# -24V-8_V0_2.net
KiCad netlist of a schematic drawn in Altium Designer
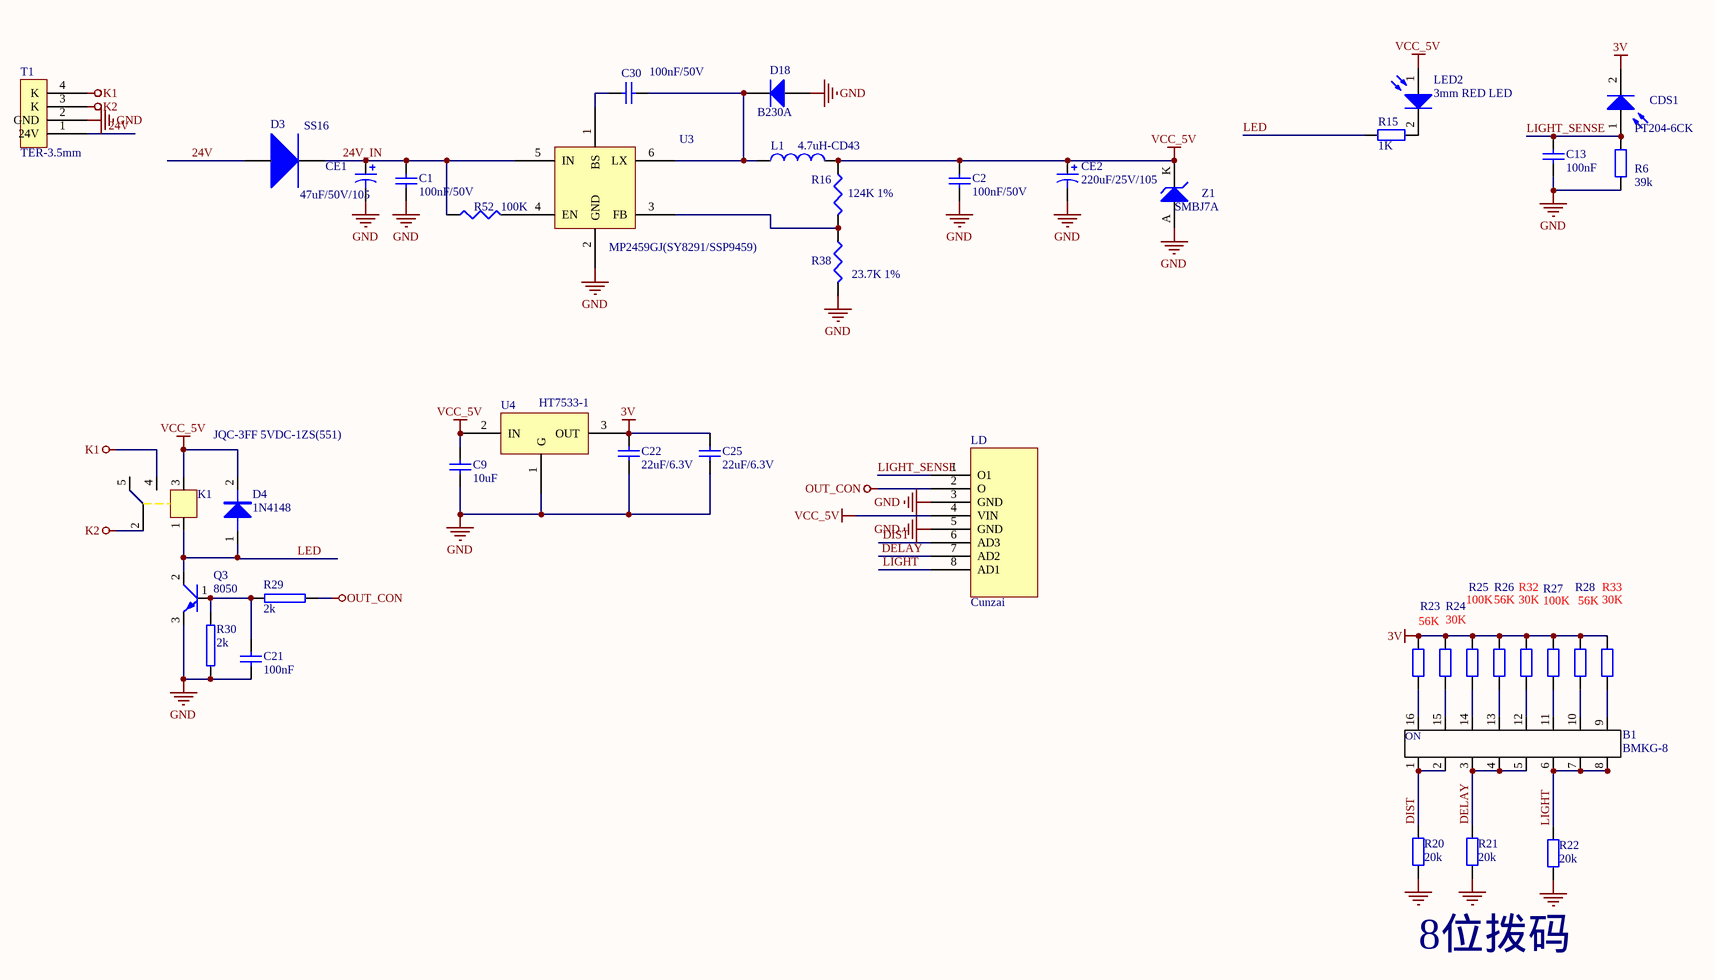
[diagram p0: 存在感应灯控模块-24V-8位拨码V0.2.schdoc]

(export (version "E")
  (design (tool "Eeschema 10.0.6"))
  (components
    (comp (ref "B1") (value "BMKG-8") (footprint "BMKG-8") (libsource (lib "灯控模组V2.0") (part "BMKG-8")))
    (comp (ref "C1")
      (value "100nF/50V")
      (footprint "0603")
      (description "Capacitor (Semiconductor SIM Model)")
      (fields (field (name "PUBLISHER") "Altium Limited"))
      (libsource (lib "Miscellaneous Devices") (part "Cap Semi"))
    )
    (comp (ref "C2")
      (value "100nF/50V")
      (footprint "0603")
      (description "Capacitor (Semiconductor SIM Model)")
      (fields (field (name "PUBLISHER") "Altium Limited"))
      (libsource (lib "Miscellaneous Devices") (part "Cap Semi"))
    )
    (comp (ref "C9")
      (value "10uF")
      (footprint "C0603")
      (description "Capacitor")
      (fields (field (name "PUBLISHER") "Altium Limited"))
      (libsource (lib "Miscellaneous Devices") (part "Cap"))
    )
    (comp (ref "C13")
      (value "100nF")
      (footprint "C0603")
      (description "Capacitor")
      (fields (field (name "PUBLISHER") "Altium Limited"))
      (libsource (lib "Miscellaneous Devices") (part "Cap"))
    )
    (comp (ref "C21")
      (value "100nF")
      (footprint "C0603")
      (description "Capacitor")
      (fields (field (name "PUBLISHER") "Altium Limited"))
      (libsource (lib "Miscellaneous Devices") (part "Cap"))
    )
    (comp (ref "C22")
      (value "22uF/6.3V")
      (footprint "C0603")
      (description "Capacitor")
      (fields (field (name "PUBLISHER") "Altium Limited"))
      (libsource (lib "Miscellaneous Devices") (part "Cap"))
    )
    (comp (ref "C25")
      (value "22uF/6.3V")
      (footprint "C0603")
      (description "Capacitor")
      (fields (field (name "PUBLISHER") "Altium Limited"))
      (libsource (lib "Miscellaneous Devices") (part "Cap"))
    )
    (comp (ref "C30")
      (value "100nF/50V")
      (footprint "0603")
      (description "Capacitor (Semiconductor SIM Model)")
      (fields (field (name "PUBLISHER") "Altium Limited"))
      (libsource (lib "Miscellaneous Devices") (part "Cap Semi"))
    )
    (comp (ref "CDS1")
      (value "PT204-6CK")
      (footprint "LED-3MM")
      (description "Photosensitive Diode")
      (fields (field (name "PUBLISHER") "Altium Limited"))
      (libsource (lib "Miscellaneous Devices") (part "Photo Sen"))
    )
    (comp (ref "CE1")
      (value "47uF/50V/105")
      (footprint "DIPC6X12")
      (description "Polarized Capacitor (Radial)")
      (fields (field (name "PUBLISHER") "Altium Limited"))
      (libsource (lib "Miscellaneous Devices") (part "Cap Pol1"))
    )
    (comp (ref "CE2")
      (value "220uF/25V/105")
      (footprint "DIPC6X12")
      (description "Polarized Capacitor (Radial)")
      (fields (field (name "PUBLISHER") "Altium Limited"))
      (libsource (lib "Miscellaneous Devices") (part "Cap Pol1"))
    )
    (comp (ref "D3") (value "SS16") (footprint "SMA") (libsource (lib "微波红外双鉴电路") (part "SS14")))
    (comp (ref "D4")
      (value "1N4148")
      (footprint "SOD123")
      (description "Diode")
      (libsource (lib "*") (part "DIODE"))
    )
    (comp (ref "D18")
      (value "B230A")
      (footprint "SMA")
      (description "1 Amp General Purpose Rectifier")
      (fields (field (name "PUBLISHER") "Altium Limited"))
      (libsource (lib "Miscellaneous Devices") (part "Diode 1N4007"))
    )
    (comp (ref "K1") (value "JQC-3FF 5VDC-1ZS(551)") (footprint "JQC-3FF") (libsource (lib "*") (part "JDQ")))
    (comp (ref "L1")
      (value "4.7uH-CD43")
      (footprint "CDRH3D16")
      (description "Inductor")
      (fields (field (name "PUBLISHER") "Altium Limited"))
      (libsource (lib "Miscellaneous Devices") (part "Inductor"))
    )
    (comp (ref "LD")
      (value "Cunzai")
      (footprint "LDCUNZAI")
      (libsource (lib "存在感应灯控模块-24V-8位拨码") (part "Cunzai"))
    )
    (comp (ref "LED2")
      (value "3mm RED LED")
      (footprint "LED-3MM")
      (description "Photosensitive Diode")
      (fields (field (name "PUBLISHER") "Altium Limited"))
      (libsource (lib "Miscellaneous Devices") (part "Photo Sen"))
    )
    (comp (ref "Q3") (value "8050") (footprint "SOT23") (libsource (lib "*") (part "8050")))
    (comp (ref "R6")
      (value "39k")
      (footprint "R0603")
      (description "Resistor")
      (fields (field (name "Comment") "Res2") (field (name "PUBLISHER") "Altium Limited"))
      (libsource (lib "Miscellaneous Devices") (part "Res2"))
    )
    (comp (ref "R15")
      (value "1K")
      (footprint "R0603")
      (description "Resistor")
      (fields (field (name "Comment") "Res2") (field (name "PUBLISHER") "Altium Limited"))
      (libsource (lib "") (part "Res2_1"))
    )
    (comp (ref "R16")
      (value "124K 1%")
      (footprint "0603")
      (description "Resistor")
      (fields (field (name "PUBLISHER") "Altium Limited"))
      (libsource (lib "Miscellaneous Devices") (part "Res3"))
    )
    (comp (ref "R20")
      (value "20k")
      (footprint "R0603")
      (description "Resistor")
      (fields (field (name "PUBLISHER") "Altium Limited"))
      (libsource (lib "*") (part "Res2"))
    )
    (comp (ref "R21")
      (value "20k")
      (footprint "R0603")
      (description "Resistor")
      (fields (field (name "PUBLISHER") "Altium Limited"))
      (libsource (lib "*") (part "Res2"))
    )
    (comp (ref "R22")
      (value "20k")
      (footprint "R0603")
      (description "Resistor")
      (fields (field (name "PUBLISHER") "Altium Limited"))
      (libsource (lib "*") (part "Res2"))
    )
    (comp (ref "R23")
      (value "56K")
      (footprint "R0603")
      (description "Resistor")
      (fields (field (name "PUBLISHER") "Altium Limited"))
      (libsource (lib "*") (part "Res2"))
    )
    (comp (ref "R24")
      (value "30K")
      (footprint "R0603")
      (description "Resistor")
      (fields (field (name "PUBLISHER") "Altium Limited"))
      (libsource (lib "*") (part "Res2"))
    )
    (comp (ref "R25")
      (value "100K")
      (footprint "R0603")
      (description "Resistor")
      (fields (field (name "PUBLISHER") "Altium Limited"))
      (libsource (lib "*") (part "Res2"))
    )
    (comp (ref "R26")
      (value "56K")
      (footprint "R0603")
      (description "Resistor")
      (fields (field (name "PUBLISHER") "Altium Limited"))
      (libsource (lib "*") (part "Res2"))
    )
    (comp (ref "R27")
      (value "100K")
      (footprint "R0603")
      (description "Resistor")
      (fields (field (name "PUBLISHER") "Altium Limited"))
      (libsource (lib "*") (part "Res2"))
    )
    (comp (ref "R28")
      (value "56K")
      (footprint "R0603")
      (description "Resistor")
      (fields (field (name "PUBLISHER") "Altium Limited"))
      (libsource (lib "*") (part "Res2"))
    )
    (comp (ref "R29") (value "2k") (footprint "SR0603") (libsource (lib "*") (part "RES")))
    (comp (ref "R30") (value "2k") (footprint "SR0603") (libsource (lib "*") (part "RES")))
    (comp (ref "R32")
      (value "30K")
      (footprint "R0603")
      (description "Resistor")
      (fields (field (name "PUBLISHER") "Altium Limited"))
      (libsource (lib "*") (part "Res2"))
    )
    (comp (ref "R33")
      (value "30K")
      (footprint "R0603")
      (description "Resistor")
      (fields (field (name "PUBLISHER") "Altium Limited"))
      (libsource (lib "*") (part "Res2"))
    )
    (comp (ref "R38")
      (value "23.7K 1%")
      (footprint "0603")
      (description "Resistor")
      (fields (field (name "PUBLISHER") "Altium Limited"))
      (libsource (lib "Miscellaneous Devices") (part "Res3"))
    )
    (comp (ref "R52")
      (value "100K")
      (footprint "0603")
      (description "Resistor")
      (fields (field (name "PUBLISHER") "Altium Limited"))
      (libsource (lib "Miscellaneous Devices") (part "Res3"))
    )
    (comp (ref "T1")
      (value "TER-3.5mm")
      (footprint "4-KKK")
      (libsource (lib "灯控模块-V3.3-(101&102&100-2)-24V-8位拨码") (part "TER-3.5mm"))
    )
    (comp (ref "U3")
      (value "MP2459GJ(SY8291/SSP9459)")
      (footprint "SOT23-6")
      (libsource (lib "SPECIAL-L-V6.6") (part "SY8120B"))
    )
    (comp (ref "U4") (value "HT7533-1") (footprint "SOT-89") (libsource (lib "MYLIB") (part "12S33")))
    (comp (ref "Z1")
      (value "SMBJ7A")
      (footprint "SMB")
      (description "Zener Diode")
      (fields (field (name "PUBLISHER") "Altium Limited"))
      (libsource (lib "Miscellaneous Devices") (part "D Zener"))
    )
  )
  (nets
    (net (code "1") (name "/24V") (class "Default")
      (node (ref "D3") (pin "1") (pinfunction "B_1") (pintype "passive"))
      (node (ref "T1") (pin "1") (pinfunction "24V_1") (pintype "passive"))
    )
    (net (code "2") (name "/24V_IN") (class "Default")
      (node (ref "C1") (pin "2") (pinfunction "2_2") (pintype "passive"))
      (node (ref "CE1") (pin "1") (pinfunction "1_1") (pintype "passive"))
      (node (ref "D3") (pin "2") (pinfunction "C_2") (pintype "passive"))
      (node (ref "R52") (pin "1") (pinfunction "1_1") (pintype "passive"))
      (node (ref "U3") (pin "5") (pinfunction "IN_5") (pintype "passive"))
    )
    (net (code "3") (name "/DELAY") (class "Default")
      (node (ref "B1") (pin "3") (pintype "passive"))
      (node (ref "B1") (pin "4") (pintype "passive"))
      (node (ref "B1") (pin "5") (pintype "passive"))
      (node (ref "LD") (pin "7") (pinfunction "AD2_7") (pintype "passive"))
      (node (ref "R21") (pin "2") (pinfunction "2_2") (pintype "passive"))
    )
    (net (code "4") (name "/DIST") (class "Default")
      (node (ref "B1") (pin "1") (pintype "passive"))
      (node (ref "B1") (pin "2") (pintype "passive"))
      (node (ref "LD") (pin "6") (pinfunction "AD3_6") (pintype "passive"))
      (node (ref "R20") (pin "2") (pinfunction "2_2") (pintype "passive"))
    )
    (net (code "5") (name "/LED") (class "Default")
      (node (ref "D4") (pin "1") (pintype "passive"))
      (node (ref "K1") (pin "1") (pintype "passive"))
      (node (ref "Q3") (pin "2") (pinfunction "E_2") (pintype "passive"))
      (node (ref "R15") (pin "2") (pinfunction "2_2") (pintype "passive"))
    )
    (net (code "6") (name "/LIGHT") (class "Default")
      (node (ref "B1") (pin "6") (pintype "passive"))
      (node (ref "B1") (pin "7") (pintype "passive"))
      (node (ref "B1") (pin "8") (pintype "passive"))
      (node (ref "LD") (pin "8") (pinfunction "AD1_8") (pintype "passive"))
      (node (ref "R22") (pin "2") (pinfunction "2_2") (pintype "passive"))
    )
    (net (code "7") (name "/LIGHT_SENSE") (class "Default")
      (node (ref "C13") (pin "2") (pinfunction "2_2") (pintype "passive"))
      (node (ref "CDS1") (pin "1") (pinfunction "A_1") (pintype "passive"))
      (node (ref "LD") (pin "1") (pinfunction "O1_1") (pintype "passive"))
      (node (ref "R6") (pin "2") (pinfunction "2_2") (pintype "passive"))
    )
    (net (code "8") (name "3V") (class "Default")
      (node (ref "C22") (pin "1") (pinfunction "1_1") (pintype "passive"))
      (node (ref "C25") (pin "1") (pinfunction "1_1") (pintype "passive"))
      (node (ref "CDS1") (pin "2") (pinfunction "K_2") (pintype "passive"))
      (node (ref "R23") (pin "2") (pinfunction "2_2") (pintype "passive"))
      (node (ref "R24") (pin "2") (pinfunction "2_2") (pintype "passive"))
      (node (ref "R25") (pin "2") (pinfunction "2_2") (pintype "passive"))
      (node (ref "R26") (pin "2") (pinfunction "2_2") (pintype "passive"))
      (node (ref "R27") (pin "2") (pinfunction "2_2") (pintype "passive"))
      (node (ref "R28") (pin "2") (pinfunction "2_2") (pintype "passive"))
      (node (ref "R32") (pin "2") (pinfunction "2_2") (pintype "passive"))
      (node (ref "R33") (pin "2") (pinfunction "2_2") (pintype "passive"))
      (node (ref "U4") (pin "3") (pinfunction "OUT_3") (pintype "passive"))
    )
    (net (code "9") (name "GND") (class "Default")
      (node (ref "C1") (pin "1") (pinfunction "1_1") (pintype "passive"))
      (node (ref "C13") (pin "1") (pinfunction "1_1") (pintype "passive"))
      (node (ref "C2") (pin "1") (pinfunction "1_1") (pintype "passive"))
      (node (ref "C21") (pin "2") (pinfunction "2_2") (pintype "passive"))
      (node (ref "C22") (pin "2") (pinfunction "2_2") (pintype "passive"))
      (node (ref "C25") (pin "2") (pinfunction "2_2") (pintype "passive"))
      (node (ref "C9") (pin "2") (pinfunction "2_2") (pintype "passive"))
      (node (ref "CE1") (pin "2") (pinfunction "2_2") (pintype "passive"))
      (node (ref "CE2") (pin "2") (pinfunction "2_2") (pintype "passive"))
      (node (ref "D18") (pin "1") (pinfunction "A_1") (pintype "passive"))
      (node (ref "LD") (pin "3") (pinfunction "GND_3") (pintype "passive"))
      (node (ref "LD") (pin "5") (pinfunction "GND_5") (pintype "passive"))
      (node (ref "Q3") (pin "3") (pinfunction "C_3") (pintype "passive"))
      (node (ref "R20") (pin "1") (pinfunction "1_1") (pintype "passive"))
      (node (ref "R21") (pin "1") (pinfunction "1_1") (pintype "passive"))
      (node (ref "R22") (pin "1") (pinfunction "1_1") (pintype "passive"))
      (node (ref "R30") (pin "1") (pinfunction "1_1") (pintype "passive"))
      (node (ref "R38") (pin "2") (pinfunction "2_2") (pintype "passive"))
      (node (ref "R6") (pin "1") (pinfunction "1_1") (pintype "passive"))
      (node (ref "T1") (pin "2") (pinfunction "GND_2") (pintype "passive"))
      (node (ref "U3") (pin "2") (pinfunction "GND_2") (pintype "passive"))
      (node (ref "U4") (pin "1") (pinfunction "G_1") (pintype "passive"))
      (node (ref "Z1") (pin "A") (pinfunction "A_A") (pintype "passive"))
    )
    (net (code "10") (name "K1") (class "Default")
      (node (ref "K1") (pin "4") (pintype "passive"))
      (node (ref "T1") (pin "4") (pinfunction "K_4") (pintype "passive"))
    )
    (net (code "11") (name "K2") (class "Default")
      (node (ref "K1") (pin "2") (pintype "passive"))
      (node (ref "T1") (pin "3") (pinfunction "K_3") (pintype "passive"))
    )
    (net (code "12") (name "Net-(B1-Pad9)") (class "Default")
      (node (ref "B1") (pin "9") (pintype "passive"))
      (node (ref "R33") (pin "1") (pinfunction "1_1") (pintype "passive"))
    )
    (net (code "13") (name "Net-(B1-Pad10)") (class "Default")
      (node (ref "B1") (pin "10") (pintype "passive"))
      (node (ref "R28") (pin "1") (pinfunction "1_1") (pintype "passive"))
    )
    (net (code "14") (name "Net-(B1-Pad11)") (class "Default")
      (node (ref "B1") (pin "11") (pintype "passive"))
      (node (ref "R27") (pin "1") (pinfunction "1_1") (pintype "passive"))
    )
    (net (code "15") (name "Net-(B1-Pad12)") (class "Default")
      (node (ref "B1") (pin "12") (pintype "passive"))
      (node (ref "R32") (pin "1") (pinfunction "1_1") (pintype "passive"))
    )
    (net (code "16") (name "Net-(B1-Pad13)") (class "Default")
      (node (ref "B1") (pin "13") (pintype "passive"))
      (node (ref "R26") (pin "1") (pinfunction "1_1") (pintype "passive"))
    )
    (net (code "17") (name "Net-(B1-Pad14)") (class "Default")
      (node (ref "B1") (pin "14") (pintype "passive"))
      (node (ref "R25") (pin "1") (pinfunction "1_1") (pintype "passive"))
    )
    (net (code "18") (name "Net-(B1-Pad15)") (class "Default")
      (node (ref "B1") (pin "15") (pintype "passive"))
      (node (ref "R24") (pin "1") (pinfunction "1_1") (pintype "passive"))
    )
    (net (code "19") (name "Net-(B1-Pad16)") (class "Default")
      (node (ref "B1") (pin "16") (pintype "passive"))
      (node (ref "R23") (pin "1") (pinfunction "1_1") (pintype "passive"))
    )
    (net (code "20") (name "Net-(D18-K)") (class "Default")
      (node (ref "C30") (pin "1") (pinfunction "1_1") (pintype "passive"))
      (node (ref "D18") (pin "2") (pinfunction "K_2") (pintype "passive"))
      (node (ref "L1") (pin "1") (pinfunction "1_1") (pintype "passive"))
      (node (ref "U3") (pin "6") (pinfunction "LX_6") (pintype "passive"))
    )
    (net (code "21") (name "Net-(LED2-K)") (class "Default")
      (node (ref "LED2") (pin "2") (pinfunction "K_2") (pintype "passive"))
      (node (ref "R15") (pin "1") (pinfunction "1_1") (pintype "passive"))
    )
    (net (code "22") (name "Net-(Q3-B)") (class "Default")
      (node (ref "C21") (pin "1") (pinfunction "1_1") (pintype "passive"))
      (node (ref "Q3") (pin "1") (pinfunction "B_1") (pintype "passive"))
      (node (ref "R29") (pin "1") (pinfunction "1_1") (pintype "passive"))
      (node (ref "R30") (pin "2") (pinfunction "2_2") (pintype "passive"))
    )
    (net (code "23") (name "Net-(U3-BS)") (class "Default")
      (node (ref "C30") (pin "2") (pinfunction "2_2") (pintype "passive"))
      (node (ref "U3") (pin "1") (pinfunction "BS_1") (pintype "passive"))
    )
    (net (code "24") (name "Net-(U3-EN)") (class "Default")
      (node (ref "R52") (pin "2") (pinfunction "2_2") (pintype "passive"))
      (node (ref "U3") (pin "4") (pinfunction "EN_4") (pintype "passive"))
    )
    (net (code "25") (name "Net-(U3-FB)") (class "Default")
      (node (ref "R16") (pin "2") (pinfunction "2_2") (pintype "passive"))
      (node (ref "R38") (pin "1") (pinfunction "1_1") (pintype "passive"))
      (node (ref "U3") (pin "3") (pinfunction "FB_3") (pintype "passive"))
    )
    (net (code "26") (name "OUT_CON") (class "Default")
      (node (ref "LD") (pin "2") (pinfunction "O_2") (pintype "passive"))
      (node (ref "R29") (pin "2") (pinfunction "2_2") (pintype "passive"))
    )
    (net (code "27") (name "VCC_5V") (class "Default")
      (node (ref "C2") (pin "2") (pinfunction "2_2") (pintype "passive"))
      (node (ref "C9") (pin "1") (pinfunction "1_1") (pintype "passive"))
      (node (ref "CE2") (pin "1") (pinfunction "1_1") (pintype "passive"))
      (node (ref "D4") (pin "2") (pintype "passive"))
      (node (ref "K1") (pin "3") (pintype "passive"))
      (node (ref "L1") (pin "2") (pinfunction "2_2") (pintype "passive"))
      (node (ref "LD") (pin "4") (pinfunction "VIN_4") (pintype "passive"))
      (node (ref "LED2") (pin "1") (pinfunction "A_1") (pintype "passive"))
      (node (ref "R16") (pin "1") (pinfunction "1_1") (pintype "passive"))
      (node (ref "U4") (pin "2") (pinfunction "IN_2") (pintype "passive"))
      (node (ref "Z1") (pin "K") (pinfunction "K_K") (pintype "passive"))
    )
    (net (code "28") (name "unconnected-(K1-Pad5)") (class "Default")
      (node (ref "K1") (pin "5") (pintype "passive"))
    )
  )
)
